# dip_picker.net
KiCad netlist of a schematic drawn in EAGLE
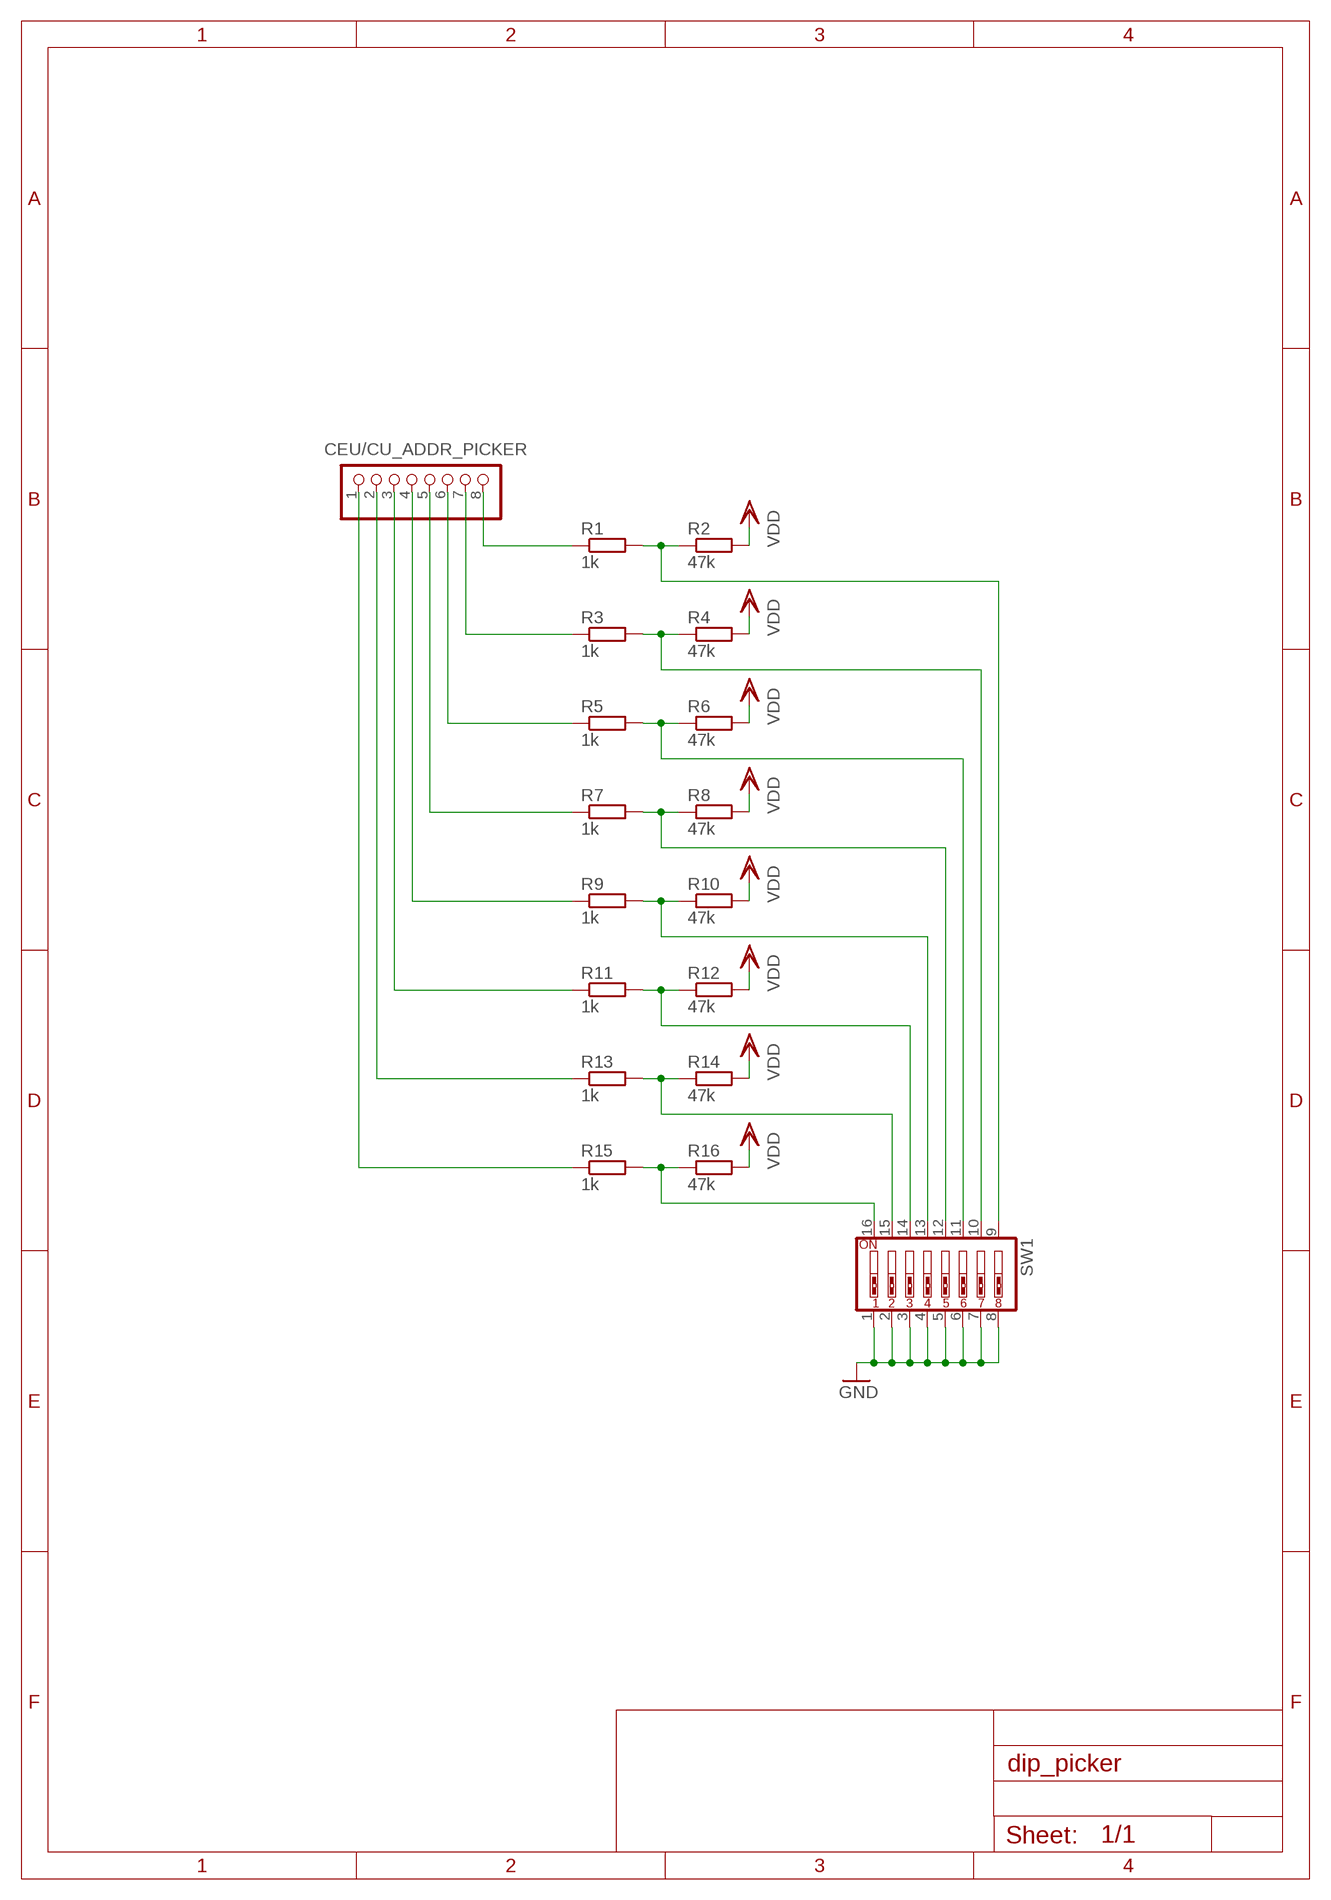
[diagram p0: schematic, sheet 1]

(export (version "E")
  (design (tool "Eeschema 10.0.6"))
  (components
    (comp (ref "CEU/CU_ADDR_PICKER")
      (value "PINHD-1X8")
      (footprint "eagle-import:1X08")
      (libsource (lib "eagle-import") (part "PINHD-1X8"))
    )
    (comp (ref "R1")
      (value "1k")
      (footprint "eagle-import:0207_7")
      (libsource (lib "eagle-import") (part "R-EU_0207/7"))
    )
    (comp (ref "R2")
      (value "47k")
      (footprint "eagle-import:0207_7")
      (libsource (lib "eagle-import") (part "R-EU_0207/7"))
    )
    (comp (ref "R3")
      (value "1k")
      (footprint "eagle-import:0207_7")
      (libsource (lib "eagle-import") (part "R-EU_0207/7"))
    )
    (comp (ref "R4")
      (value "47k")
      (footprint "eagle-import:0207_7")
      (libsource (lib "eagle-import") (part "R-EU_0207/7"))
    )
    (comp (ref "R5")
      (value "1k")
      (footprint "eagle-import:0207_7")
      (libsource (lib "eagle-import") (part "R-EU_0207/7"))
    )
    (comp (ref "R6")
      (value "47k")
      (footprint "eagle-import:0207_7")
      (libsource (lib "eagle-import") (part "R-EU_0207/7"))
    )
    (comp (ref "R7")
      (value "1k")
      (footprint "eagle-import:0207_7")
      (libsource (lib "eagle-import") (part "R-EU_0207/7"))
    )
    (comp (ref "R8")
      (value "47k")
      (footprint "eagle-import:0207_7")
      (libsource (lib "eagle-import") (part "R-EU_0207/7"))
    )
    (comp (ref "R9")
      (value "1k")
      (footprint "eagle-import:0207_7")
      (libsource (lib "eagle-import") (part "R-EU_0207/7"))
    )
    (comp (ref "R10")
      (value "47k")
      (footprint "eagle-import:0207_7")
      (libsource (lib "eagle-import") (part "R-EU_0207/7"))
    )
    (comp (ref "R11")
      (value "1k")
      (footprint "eagle-import:0207_7")
      (libsource (lib "eagle-import") (part "R-EU_0207/7"))
    )
    (comp (ref "R12")
      (value "47k")
      (footprint "eagle-import:0207_7")
      (libsource (lib "eagle-import") (part "R-EU_0207/7"))
    )
    (comp (ref "R13")
      (value "1k")
      (footprint "eagle-import:0207_7")
      (libsource (lib "eagle-import") (part "R-EU_0207/7"))
    )
    (comp (ref "R14")
      (value "47k")
      (footprint "eagle-import:0207_7")
      (libsource (lib "eagle-import") (part "R-EU_0207/7"))
    )
    (comp (ref "R15")
      (value "1k")
      (footprint "eagle-import:0207_7")
      (libsource (lib "eagle-import") (part "R-EU_0207/7"))
    )
    (comp (ref "R16")
      (value "47k")
      (footprint "eagle-import:0207_7")
      (libsource (lib "eagle-import") (part "R-EU_0207/7"))
    )
    (comp (ref "SW1")
      (value "SW_DIP-8")
      (footprint "eagle-import:EDG-08")
      (libsource (lib "eagle-import") (part "SW_DIP-8"))
    )
  )
  (nets
    (net (code "1") (name "GND") (class "Default")
      (node (ref "SW1") (pin "1") (pinfunction "1_1") (pintype "passive"))
      (node (ref "SW1") (pin "2") (pinfunction "2_2") (pintype "passive"))
      (node (ref "SW1") (pin "3") (pinfunction "3_3") (pintype "passive"))
      (node (ref "SW1") (pin "4") (pinfunction "4_4") (pintype "passive"))
      (node (ref "SW1") (pin "5") (pinfunction "5_5") (pintype "passive"))
      (node (ref "SW1") (pin "6") (pinfunction "6_6") (pintype "passive"))
      (node (ref "SW1") (pin "7") (pinfunction "7_7") (pintype "passive"))
      (node (ref "SW1") (pin "8") (pinfunction "8_8") (pintype "passive"))
    )
    (net (code "2") (name "Net-(CEU/CU_ADDR_PICKER-Pad1)") (class "Default")
      (node (ref "CEU/CU_ADDR_PICKER") (pin "1") (pinfunction "1_1") (pintype "passive"))
      (node (ref "R15") (pin "1") (pinfunction "1_1") (pintype "passive"))
    )
    (net (code "3") (name "Net-(CEU/CU_ADDR_PICKER-Pad2)") (class "Default")
      (node (ref "CEU/CU_ADDR_PICKER") (pin "2") (pinfunction "2_2") (pintype "passive"))
      (node (ref "R13") (pin "1") (pinfunction "1_1") (pintype "passive"))
    )
    (net (code "4") (name "Net-(CEU/CU_ADDR_PICKER-Pad3)") (class "Default")
      (node (ref "CEU/CU_ADDR_PICKER") (pin "3") (pinfunction "3_3") (pintype "passive"))
      (node (ref "R11") (pin "1") (pinfunction "1_1") (pintype "passive"))
    )
    (net (code "5") (name "Net-(CEU/CU_ADDR_PICKER-Pad4)") (class "Default")
      (node (ref "CEU/CU_ADDR_PICKER") (pin "4") (pinfunction "4_4") (pintype "passive"))
      (node (ref "R9") (pin "1") (pinfunction "1_1") (pintype "passive"))
    )
    (net (code "6") (name "Net-(CEU/CU_ADDR_PICKER-Pad5)") (class "Default")
      (node (ref "CEU/CU_ADDR_PICKER") (pin "5") (pinfunction "5_5") (pintype "passive"))
      (node (ref "R7") (pin "1") (pinfunction "1_1") (pintype "passive"))
    )
    (net (code "7") (name "Net-(CEU/CU_ADDR_PICKER-Pad6)") (class "Default")
      (node (ref "CEU/CU_ADDR_PICKER") (pin "6") (pinfunction "6_6") (pintype "passive"))
      (node (ref "R5") (pin "1") (pinfunction "1_1") (pintype "passive"))
    )
    (net (code "8") (name "Net-(CEU/CU_ADDR_PICKER-Pad7)") (class "Default")
      (node (ref "CEU/CU_ADDR_PICKER") (pin "7") (pinfunction "7_7") (pintype "passive"))
      (node (ref "R3") (pin "1") (pinfunction "1_1") (pintype "passive"))
    )
    (net (code "9") (name "Net-(CEU/CU_ADDR_PICKER-Pad8)") (class "Default")
      (node (ref "CEU/CU_ADDR_PICKER") (pin "8") (pinfunction "8_8") (pintype "passive"))
      (node (ref "R1") (pin "1") (pinfunction "1_1") (pintype "passive"))
    )
    (net (code "10") (name "Net-(R1-Pad2)") (class "Default")
      (node (ref "R1") (pin "2") (pinfunction "2_2") (pintype "passive"))
      (node (ref "R2") (pin "1") (pinfunction "1_1") (pintype "passive"))
      (node (ref "SW1") (pin "9") (pinfunction "9_9") (pintype "passive"))
    )
    (net (code "11") (name "Net-(R3-Pad2)") (class "Default")
      (node (ref "R3") (pin "2") (pinfunction "2_2") (pintype "passive"))
      (node (ref "R4") (pin "1") (pinfunction "1_1") (pintype "passive"))
      (node (ref "SW1") (pin "10") (pinfunction "10_10") (pintype "passive"))
    )
    (net (code "12") (name "Net-(R5-Pad2)") (class "Default")
      (node (ref "R5") (pin "2") (pinfunction "2_2") (pintype "passive"))
      (node (ref "R6") (pin "1") (pinfunction "1_1") (pintype "passive"))
      (node (ref "SW1") (pin "11") (pinfunction "11_11") (pintype "passive"))
    )
    (net (code "13") (name "Net-(R7-Pad2)") (class "Default")
      (node (ref "R7") (pin "2") (pinfunction "2_2") (pintype "passive"))
      (node (ref "R8") (pin "1") (pinfunction "1_1") (pintype "passive"))
      (node (ref "SW1") (pin "12") (pinfunction "12_12") (pintype "passive"))
    )
    (net (code "14") (name "Net-(R10-Pad1)") (class "Default")
      (node (ref "R10") (pin "1") (pinfunction "1_1") (pintype "passive"))
      (node (ref "R9") (pin "2") (pinfunction "2_2") (pintype "passive"))
      (node (ref "SW1") (pin "13") (pinfunction "13_13") (pintype "passive"))
    )
    (net (code "15") (name "Net-(R11-Pad2)") (class "Default")
      (node (ref "R11") (pin "2") (pinfunction "2_2") (pintype "passive"))
      (node (ref "R12") (pin "1") (pinfunction "1_1") (pintype "passive"))
      (node (ref "SW1") (pin "14") (pinfunction "14_14") (pintype "passive"))
    )
    (net (code "16") (name "Net-(R13-Pad2)") (class "Default")
      (node (ref "R13") (pin "2") (pinfunction "2_2") (pintype "passive"))
      (node (ref "R14") (pin "1") (pinfunction "1_1") (pintype "passive"))
      (node (ref "SW1") (pin "15") (pinfunction "15_15") (pintype "passive"))
    )
    (net (code "17") (name "Net-(R15-Pad2)") (class "Default")
      (node (ref "R15") (pin "2") (pinfunction "2_2") (pintype "passive"))
      (node (ref "R16") (pin "1") (pinfunction "1_1") (pintype "passive"))
      (node (ref "SW1") (pin "16") (pinfunction "16_16") (pintype "passive"))
    )
    (net (code "18") (name "VDD") (class "Default")
      (node (ref "R10") (pin "2") (pinfunction "2_2") (pintype "passive"))
      (node (ref "R12") (pin "2") (pinfunction "2_2") (pintype "passive"))
      (node (ref "R14") (pin "2") (pinfunction "2_2") (pintype "passive"))
      (node (ref "R16") (pin "2") (pinfunction "2_2") (pintype "passive"))
      (node (ref "R2") (pin "2") (pinfunction "2_2") (pintype "passive"))
      (node (ref "R4") (pin "2") (pinfunction "2_2") (pintype "passive"))
      (node (ref "R6") (pin "2") (pinfunction "2_2") (pintype "passive"))
      (node (ref "R8") (pin "2") (pinfunction "2_2") (pintype "passive"))
    )
  )
)
